# can.net
KiCad netlist of a schematic drawn in Altium Designer
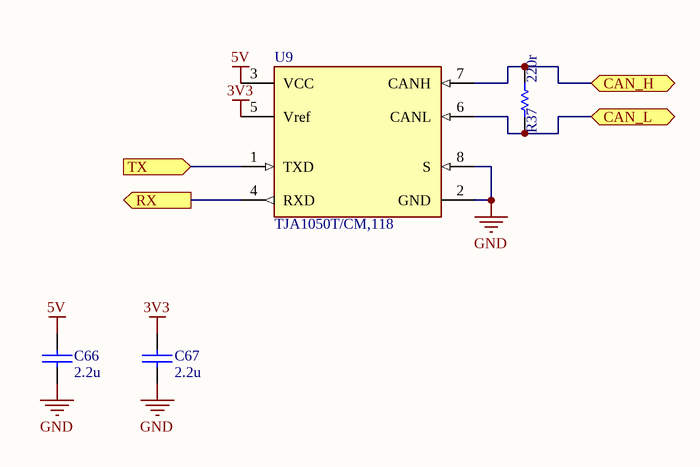
[diagram p0: can.SchDoc]

(export (version "E")
  (design (tool "Eeschema 10.0.6"))
  (components
    (comp (ref "C66")
      (value "2.2u")
      (footprint "0603C")
      (description "无极性电容")
      (libsource (lib "电容") (part "CAP"))
    )
    (comp (ref "C67")
      (value "2.2u")
      (footprint "0603C")
      (description "无极性电容")
      (libsource (lib "电容") (part "CAP"))
    )
    (comp (ref "R37") (value "220r") (footprint "0603R") (libsource (lib "电阻") (part "RES")))
    (comp (ref "U9")
      (value "TJA1050T/CM,118")
      (footprint "FP-SOT96-1-IPC_A")
      (description "IC TRANSCEIVER HALF 1/1 8SO")
      (libsource (lib "Altium Content Vault") (part "cfdefafd38a55dc0607790f57b8a78f"))
    )
  )
  (nets
    (net (code "1") (name "/CAN_H") (class "Default")
      (node (ref "R37") (pin "2") (pinfunction "2_2") (pintype "passive"))
      (node (ref "U9") (pin "7") (pinfunction "CANH_7") (pintype "input"))
    )
    (net (code "2") (name "/CAN_L") (class "Default")
      (node (ref "R37") (pin "1") (pinfunction "1_1") (pintype "passive"))
      (node (ref "U9") (pin "6") (pinfunction "CANL_6") (pintype "input"))
    )
    (net (code "3") (name "/RX") (class "Default")
      (node (ref "U9") (pin "4") (pinfunction "RXD_4") (pintype "output"))
    )
    (net (code "4") (name "/TX") (class "Default")
      (node (ref "U9") (pin "1") (pinfunction "TXD_1") (pintype "input"))
    )
    (net (code "5") (name "3V3") (class "Default")
      (node (ref "C67") (pin "2") (pinfunction "2_2") (pintype "passive"))
      (node (ref "U9") (pin "5") (pinfunction "Vref_5") (pintype "power_in"))
    )
    (net (code "6") (name "5V") (class "Default")
      (node (ref "C66") (pin "2") (pinfunction "2_2") (pintype "passive"))
      (node (ref "U9") (pin "3") (pinfunction "VCC_3") (pintype "power_in"))
    )
    (net (code "7") (name "GND") (class "Default")
      (node (ref "C66") (pin "1") (pinfunction "1_1") (pintype "passive"))
      (node (ref "C67") (pin "1") (pinfunction "1_1") (pintype "passive"))
      (node (ref "U9") (pin "2") (pinfunction "GND_2") (pintype "power_in"))
      (node (ref "U9") (pin "8") (pinfunction "S_8") (pintype "input"))
    )
  )
)
